# zumy_carrier_board.net
KiCad netlist of a schematic drawn in EAGLE
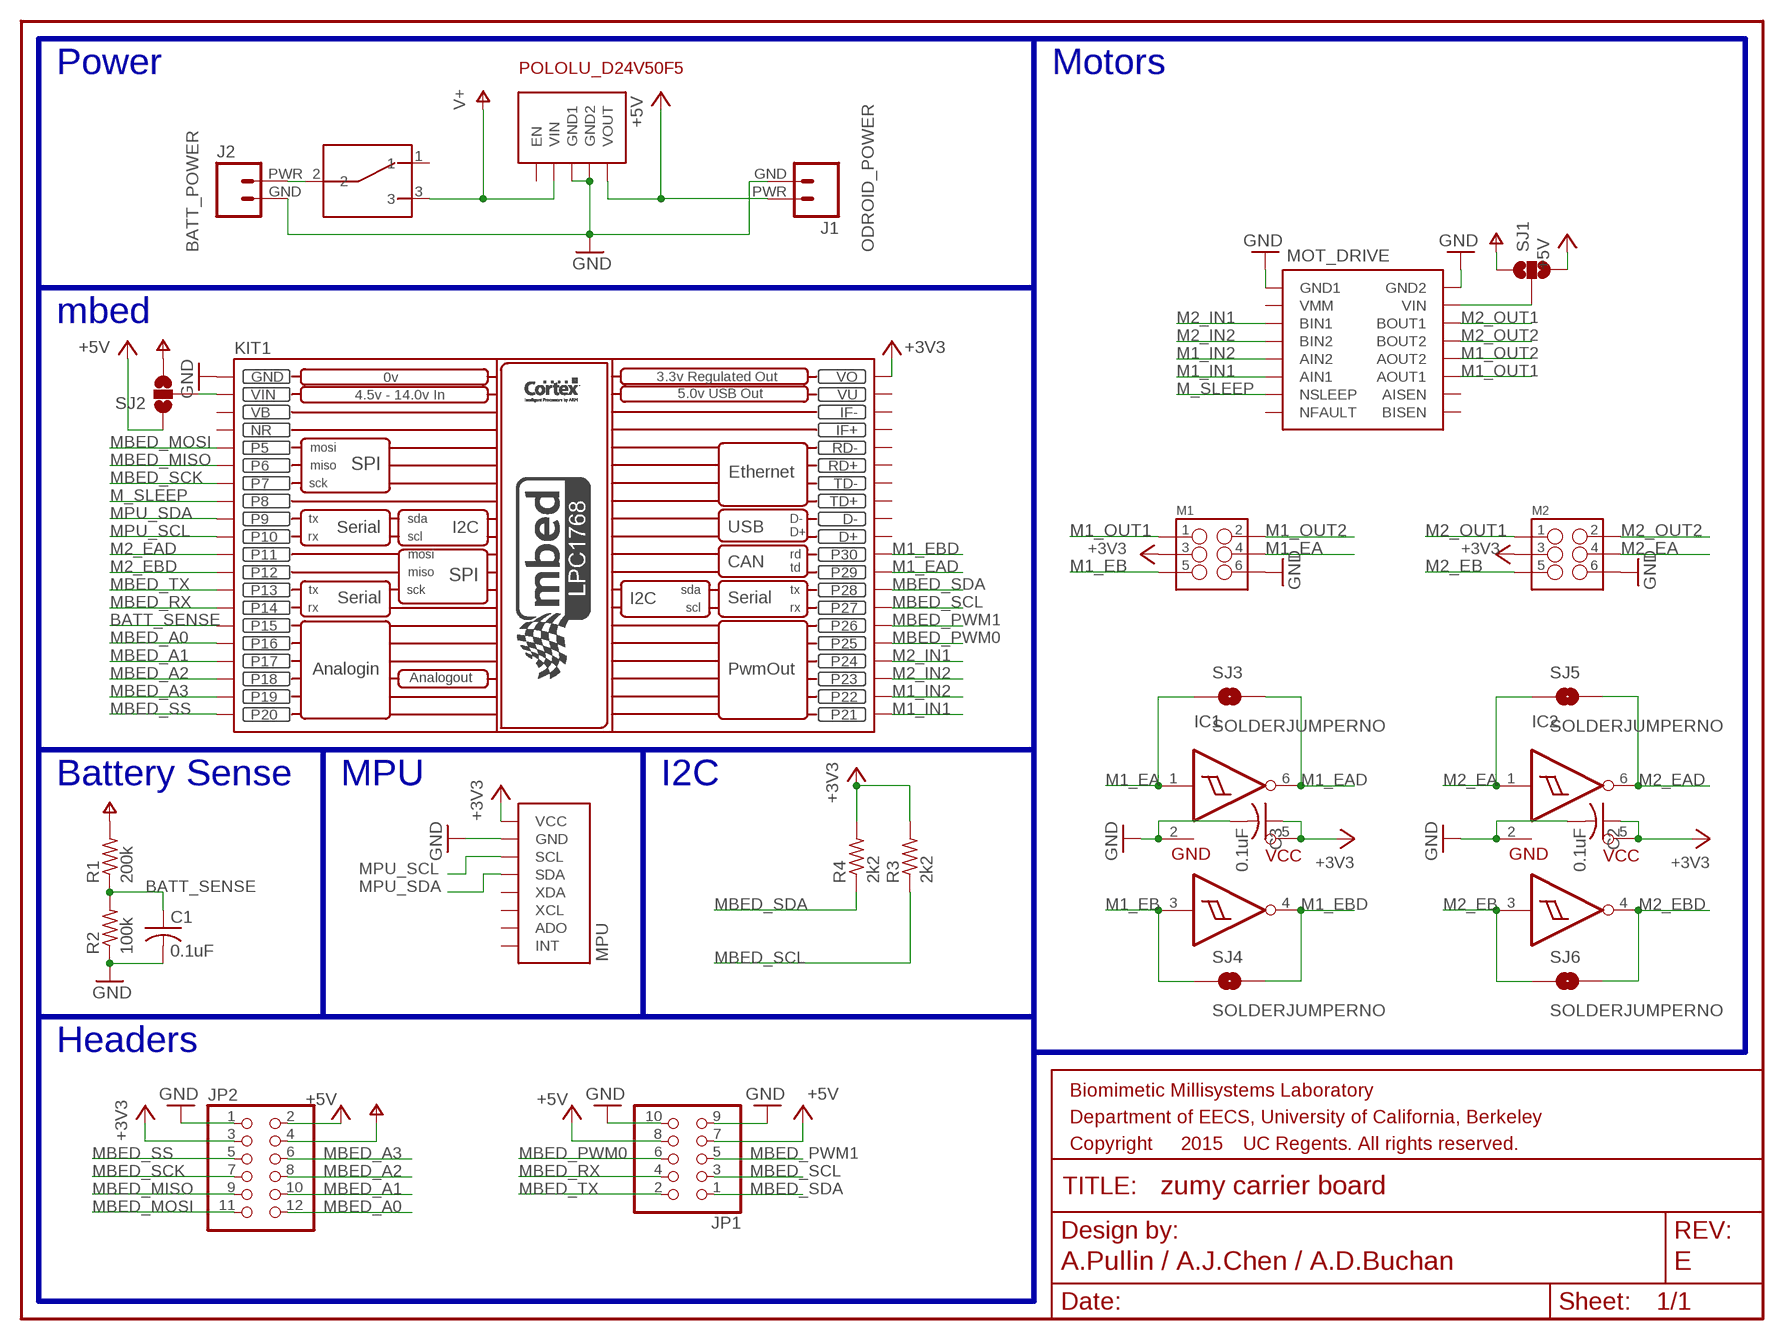
[diagram p0: schematic, sheet 1]

(export (version "E")
  (design (tool "Eeschema 10.0.6"))
  (components
    (comp (ref "C1")
      (value "0.1uF")
      (footprint "eagle-import:C1206")
      (libsource (lib "eagle-import") (part "C-USC1206"))
    )
    (comp (ref "C2")
      (value "0.1uF")
      (footprint "eagle-import:C1206")
      (libsource (lib "eagle-import") (part "C-USC1206"))
    )
    (comp (ref "C3")
      (value "0.1uF")
      (footprint "eagle-import:C1206")
      (libsource (lib "eagle-import") (part "C-USC1206"))
    )
    (comp (ref "IC1")
      (value "SN74AUP2G17")
      (footprint "eagle-import:SC-70-6")
      (libsource (lib "eagle-import") (part "SN74AUP2G17"))
    )
    (comp (ref "IC2")
      (value "SN74AUP2G17")
      (footprint "eagle-import:SC-70-6")
      (libsource (lib "eagle-import") (part "SN74AUP2G17"))
    )
    (comp (ref "J1")
      (value "ODROID_POWER")
      (footprint "eagle-import:ODOIRD_PWR")
      (libsource (lib "eagle-import") (part "ODROID_POWER"))
    )
    (comp (ref "J2")
      (value "BATT_POWER")
      (footprint "eagle-import:BATT_POWER")
      (libsource (lib "eagle-import") (part "BATT_POWER"))
    )
    (comp (ref "JP1")
      (value "PINHD-2X5")
      (footprint "eagle-import:2X05")
      (libsource (lib "eagle-import") (part "PINHD-2X5"))
    )
    (comp (ref "JP2")
      (value "PINHD-2X6")
      (footprint "eagle-import:2X06")
      (libsource (lib "eagle-import") (part "PINHD-2X6"))
    )
    (comp (ref "KIT1")
      (value "MBED_NXP_LPC1768")
      (footprint "eagle-import:MBED-KIT")
      (libsource (lib "eagle-import") (part "MBED_NXP_LPC1768"))
    )
    (comp (ref "M1")
      (value "M03X2SHROUD")
      (footprint "eagle-import:2X3-SHROUDED")
      (libsource (lib "eagle-import") (part "M03X2SHROUD"))
    )
    (comp (ref "M2")
      (value "M03X2SHROUD")
      (footprint "eagle-import:2X3-SHROUDED")
      (libsource (lib "eagle-import") (part "M03X2SHROUD"))
    )
    (comp (ref "MOT_DRIVE")
      (value "POLOLU_DRV8833_MODULE")
      (footprint "eagle-import:POLOLU_DRV8833_MODULE")
      (libsource (lib "eagle-import") (part "POLOLU_DRV8833_MODULE"))
    )
    (comp (ref "MPU")
      (value "ITG/MPU_MODULE")
      (footprint "eagle-import:ITG_MPU_MODULE")
      (libsource (lib "eagle-import") (part "ITG/MPU_MODULE"))
    )
    (comp (ref "R1")
      (value "200k")
      (footprint "eagle-import:R1206")
      (libsource (lib "eagle-import") (part "R-US_R1206"))
    )
    (comp (ref "R2")
      (value "100k")
      (footprint "eagle-import:R1206")
      (libsource (lib "eagle-import") (part "R-US_R1206"))
    )
    (comp (ref "R3")
      (value "2k2")
      (footprint "eagle-import:R1206")
      (libsource (lib "eagle-import") (part "R-US_R1206"))
    )
    (comp (ref "R4")
      (value "2k2")
      (footprint "eagle-import:R1206")
      (libsource (lib "eagle-import") (part "R-US_R1206"))
    )
    (comp (ref "SJ1")
      (value "SOLDERJUMPER_2WAYT")
      (footprint "eagle-import:SJ_2")
      (libsource (lib "eagle-import") (part "SOLDERJUMPER_2WAYT"))
    )
    (comp (ref "SJ2")
      (value "SOLDERJUMPER_2WAYT")
      (footprint "eagle-import:SJ_2")
      (libsource (lib "eagle-import") (part "SOLDERJUMPER_2WAYT"))
    )
    (comp (ref "SJ3")
      (value "SOLDERJUMPERNO")
      (footprint "eagle-import:SJ_2S-NO")
      (libsource (lib "eagle-import") (part "SOLDERJUMPERNO"))
    )
    (comp (ref "SJ4")
      (value "SOLDERJUMPERNO")
      (footprint "eagle-import:SJ_2S-NO")
      (libsource (lib "eagle-import") (part "SOLDERJUMPERNO"))
    )
    (comp (ref "SJ5")
      (value "SOLDERJUMPERNO")
      (footprint "eagle-import:SJ_2S-NO")
      (libsource (lib "eagle-import") (part "SOLDERJUMPERNO"))
    )
    (comp (ref "SJ6")
      (value "SOLDERJUMPERNO")
      (footprint "eagle-import:SJ_2S-NO")
      (libsource (lib "eagle-import") (part "SOLDERJUMPERNO"))
    )
    (comp (ref "SW1")
      (value "500SSP1S1M6QEA")
      (footprint "eagle-import:500SSP1S1M6QEA_SWITCH")
      (libsource (lib "eagle-import") (part "500SSP1S1M6QEA"))
    )
    (comp (ref "U$5")
      (value "POLOLU_D24V50F5")
      (footprint "eagle-import:POLOLU_D24V50F5")
      (libsource (lib "eagle-import") (part "POLOLU_D24V50F5"))
    )
  )
  (nets
    (net (code "1") (name "+3V3") (class "Default")
      (node (ref "C2") (pin "1") (pinfunction "1_1") (pintype "passive"))
      (node (ref "C3") (pin "1") (pinfunction "1_1") (pintype "passive"))
      (node (ref "IC1") (pin "5") (pinfunction "VCC_5") (pintype "output"))
      (node (ref "IC2") (pin "5") (pinfunction "VCC_5") (pintype "output"))
      (node (ref "JP2") (pin "3") (pinfunction "3_3") (pintype "passive"))
      (node (ref "KIT1") (pin "VOUT") (pinfunction "VO_VOUT") (pintype "power_in"))
      (node (ref "M1") (pin "3") (pinfunction "3_3") (pintype "bidirectional"))
      (node (ref "M2") (pin "3") (pinfunction "3_3") (pintype "bidirectional"))
      (node (ref "MPU") (pin "VCC") (pinfunction "VCC_VCC") (pintype "bidirectional"))
      (node (ref "R3") (pin "2") (pinfunction "2_2") (pintype "passive"))
      (node (ref "R4") (pin "2") (pinfunction "2_2") (pintype "passive"))
    )
    (net (code "2") (name "+5V") (class "Default")
      (node (ref "J1") (pin "PWR") (pinfunction "PWR_PWR") (pintype "passive"))
      (node (ref "JP1") (pin "7") (pinfunction "7_7") (pintype "passive"))
      (node (ref "JP1") (pin "8") (pinfunction "8_8") (pintype "passive"))
      (node (ref "JP2") (pin "2") (pinfunction "2_2") (pintype "passive"))
      (node (ref "SJ1") (pin "3") (pinfunction "3_3") (pintype "passive"))
      (node (ref "SJ2") (pin "1") (pinfunction "1_1") (pintype "passive"))
      (node (ref "U$5") (pin "VOUT") (pinfunction "VOUT_VOUT") (pintype "bidirectional"))
    )
    (net (code "3") (name "/BATT_SENSE") (class "Default")
      (node (ref "C1") (pin "1") (pinfunction "1_1") (pintype "passive"))
      (node (ref "KIT1") (pin "P$15") (pinfunction "P15_P$15") (pintype "bidirectional"))
      (node (ref "R1") (pin "1") (pinfunction "1_1") (pintype "passive"))
      (node (ref "R2") (pin "2") (pinfunction "2_2") (pintype "passive"))
    )
    (net (code "4") (name "/M1_EA") (class "Default")
      (node (ref "IC1") (pin "1") (pinfunction "1A_1") (pintype "input"))
      (node (ref "M1") (pin "4") (pinfunction "4_4") (pintype "bidirectional"))
      (node (ref "SJ3") (pin "1") (pinfunction "1_1") (pintype "passive"))
    )
    (net (code "5") (name "/M1_EAD") (class "Default")
      (node (ref "IC1") (pin "6") (pinfunction "1Y_6") (pintype "output"))
      (node (ref "KIT1") (pin "P$29") (pinfunction "P29_P$29") (pintype "bidirectional"))
      (node (ref "SJ3") (pin "2") (pinfunction "2_2") (pintype "passive"))
    )
    (net (code "6") (name "/M1_EB") (class "Default")
      (node (ref "IC1") (pin "3") (pinfunction "2A_3") (pintype "input"))
      (node (ref "M1") (pin "5") (pinfunction "5_5") (pintype "bidirectional"))
      (node (ref "SJ4") (pin "1") (pinfunction "1_1") (pintype "passive"))
    )
    (net (code "7") (name "/M1_EBD") (class "Default")
      (node (ref "IC1") (pin "4") (pinfunction "2Y_4") (pintype "output"))
      (node (ref "KIT1") (pin "P$30") (pinfunction "P30_P$30") (pintype "bidirectional"))
      (node (ref "SJ4") (pin "2") (pinfunction "2_2") (pintype "passive"))
    )
    (net (code "8") (name "/M1_IN1") (class "Default")
      (node (ref "KIT1") (pin "P$21") (pinfunction "P21_P$21") (pintype "bidirectional"))
      (node (ref "MOT_DRIVE") (pin "AIN1") (pinfunction "AIN1_AIN1") (pintype "bidirectional"))
    )
    (net (code "9") (name "/M1_IN2") (class "Default")
      (node (ref "KIT1") (pin "P$22") (pinfunction "P22_P$22") (pintype "bidirectional"))
      (node (ref "MOT_DRIVE") (pin "AIN2") (pinfunction "AIN2_AIN2") (pintype "bidirectional"))
    )
    (net (code "10") (name "/M1_OUT1") (class "Default")
      (node (ref "M1") (pin "1") (pinfunction "1_1") (pintype "bidirectional"))
      (node (ref "MOT_DRIVE") (pin "AOUT1") (pinfunction "AOUT1_AOUT1") (pintype "bidirectional"))
    )
    (net (code "11") (name "/M1_OUT2") (class "Default")
      (node (ref "M1") (pin "2") (pinfunction "2_2") (pintype "bidirectional"))
      (node (ref "MOT_DRIVE") (pin "AOUT2") (pinfunction "AOUT2_AOUT2") (pintype "bidirectional"))
    )
    (net (code "12") (name "/M2_EA") (class "Default")
      (node (ref "IC2") (pin "1") (pinfunction "1A_1") (pintype "input"))
      (node (ref "M2") (pin "4") (pinfunction "4_4") (pintype "bidirectional"))
      (node (ref "SJ5") (pin "1") (pinfunction "1_1") (pintype "passive"))
    )
    (net (code "13") (name "/M2_EAD") (class "Default")
      (node (ref "IC2") (pin "6") (pinfunction "1Y_6") (pintype "output"))
      (node (ref "KIT1") (pin "P$11") (pinfunction "P11_P$11") (pintype "bidirectional"))
      (node (ref "SJ5") (pin "2") (pinfunction "2_2") (pintype "passive"))
    )
    (net (code "14") (name "/M2_EB") (class "Default")
      (node (ref "IC2") (pin "3") (pinfunction "2A_3") (pintype "input"))
      (node (ref "M2") (pin "5") (pinfunction "5_5") (pintype "bidirectional"))
      (node (ref "SJ6") (pin "1") (pinfunction "1_1") (pintype "passive"))
    )
    (net (code "15") (name "/M2_EBD") (class "Default")
      (node (ref "IC2") (pin "4") (pinfunction "2Y_4") (pintype "output"))
      (node (ref "KIT1") (pin "P$12") (pinfunction "P12_P$12") (pintype "bidirectional"))
      (node (ref "SJ6") (pin "2") (pinfunction "2_2") (pintype "passive"))
    )
    (net (code "16") (name "/M2_IN1") (class "Default")
      (node (ref "KIT1") (pin "P$24") (pinfunction "P24_P$24") (pintype "bidirectional"))
      (node (ref "MOT_DRIVE") (pin "BIN1") (pinfunction "BIN1_BIN1") (pintype "bidirectional"))
    )
    (net (code "17") (name "/M2_IN2") (class "Default")
      (node (ref "KIT1") (pin "P$23") (pinfunction "P23_P$23") (pintype "bidirectional"))
      (node (ref "MOT_DRIVE") (pin "BIN2") (pinfunction "BIN2_BIN2") (pintype "bidirectional"))
    )
    (net (code "18") (name "/M2_OUT1") (class "Default")
      (node (ref "M2") (pin "1") (pinfunction "1_1") (pintype "bidirectional"))
      (node (ref "MOT_DRIVE") (pin "BOUT1") (pinfunction "BOUT1_BOUT1") (pintype "bidirectional"))
    )
    (net (code "19") (name "/M2_OUT2") (class "Default")
      (node (ref "M2") (pin "2") (pinfunction "2_2") (pintype "bidirectional"))
      (node (ref "MOT_DRIVE") (pin "BOUT2") (pinfunction "BOUT2_BOUT2") (pintype "bidirectional"))
    )
    (net (code "20") (name "/MBED_A0") (class "Default")
      (node (ref "JP2") (pin "12") (pinfunction "12_12") (pintype "passive"))
      (node (ref "KIT1") (pin "P$16") (pinfunction "P16_P$16") (pintype "bidirectional"))
    )
    (net (code "21") (name "/MBED_A1") (class "Default")
      (node (ref "JP2") (pin "10") (pinfunction "10_10") (pintype "passive"))
      (node (ref "KIT1") (pin "P$17") (pinfunction "P17_P$17") (pintype "bidirectional"))
    )
    (net (code "22") (name "/MBED_A2") (class "Default")
      (node (ref "JP2") (pin "8") (pinfunction "8_8") (pintype "passive"))
      (node (ref "KIT1") (pin "P$18") (pinfunction "P18_P$18") (pintype "bidirectional"))
    )
    (net (code "23") (name "/MBED_A3") (class "Default")
      (node (ref "JP2") (pin "6") (pinfunction "6_6") (pintype "passive"))
      (node (ref "KIT1") (pin "P$19") (pinfunction "P19_P$19") (pintype "bidirectional"))
    )
    (net (code "24") (name "/MBED_MISO") (class "Default")
      (node (ref "JP2") (pin "9") (pinfunction "9_9") (pintype "passive"))
      (node (ref "KIT1") (pin "P$6") (pinfunction "P6_P$6") (pintype "bidirectional"))
    )
    (net (code "25") (name "/MBED_MOSI") (class "Default")
      (node (ref "JP2") (pin "11") (pinfunction "11_11") (pintype "passive"))
      (node (ref "KIT1") (pin "P$5") (pinfunction "P5_P$5") (pintype "bidirectional"))
    )
    (net (code "26") (name "/MBED_PWM0") (class "Default")
      (node (ref "JP1") (pin "6") (pinfunction "6_6") (pintype "passive"))
      (node (ref "KIT1") (pin "P$25") (pinfunction "P25_P$25") (pintype "bidirectional"))
    )
    (net (code "27") (name "/MBED_PWM1") (class "Default")
      (node (ref "JP1") (pin "5") (pinfunction "5_5") (pintype "passive"))
      (node (ref "KIT1") (pin "P$26") (pinfunction "P26_P$26") (pintype "bidirectional"))
    )
    (net (code "28") (name "/MBED_RX") (class "Default")
      (node (ref "JP1") (pin "4") (pinfunction "4_4") (pintype "passive"))
      (node (ref "KIT1") (pin "P$14") (pinfunction "P14_P$14") (pintype "bidirectional"))
    )
    (net (code "29") (name "/MBED_SCK") (class "Default")
      (node (ref "JP2") (pin "7") (pinfunction "7_7") (pintype "passive"))
      (node (ref "KIT1") (pin "P$7") (pinfunction "P7_P$7") (pintype "bidirectional"))
    )
    (net (code "30") (name "/MBED_SCL") (class "Default")
      (node (ref "JP1") (pin "3") (pinfunction "3_3") (pintype "passive"))
      (node (ref "KIT1") (pin "P$27") (pinfunction "P27_P$27") (pintype "bidirectional"))
      (node (ref "R3") (pin "1") (pinfunction "1_1") (pintype "passive"))
    )
    (net (code "31") (name "/MBED_SDA") (class "Default")
      (node (ref "JP1") (pin "1") (pinfunction "1_1") (pintype "passive"))
      (node (ref "KIT1") (pin "P$28") (pinfunction "P28_P$28") (pintype "bidirectional"))
      (node (ref "R4") (pin "1") (pinfunction "1_1") (pintype "passive"))
    )
    (net (code "32") (name "/MBED_SS") (class "Default")
      (node (ref "JP2") (pin "5") (pinfunction "5_5") (pintype "passive"))
      (node (ref "KIT1") (pin "P$20") (pinfunction "P20_P$20") (pintype "bidirectional"))
    )
    (net (code "33") (name "/MBED_TX") (class "Default")
      (node (ref "JP1") (pin "2") (pinfunction "2_2") (pintype "passive"))
      (node (ref "KIT1") (pin "P$13") (pinfunction "P13_P$13") (pintype "bidirectional"))
    )
    (net (code "34") (name "/MPU_SCL") (class "Default")
      (node (ref "KIT1") (pin "P$10") (pinfunction "P10_P$10") (pintype "bidirectional"))
      (node (ref "MPU") (pin "SCL") (pinfunction "SCL_SCL") (pintype "bidirectional"))
    )
    (net (code "35") (name "/MPU_SDA") (class "Default")
      (node (ref "KIT1") (pin "P$9") (pinfunction "P9_P$9") (pintype "bidirectional"))
      (node (ref "MPU") (pin "SDA") (pinfunction "SDA_SDA") (pintype "bidirectional"))
    )
    (net (code "36") (name "/M_SLEEP") (class "Default")
      (node (ref "KIT1") (pin "P$8") (pinfunction "P8_P$8") (pintype "bidirectional"))
      (node (ref "MOT_DRIVE") (pin "NSLEEP") (pinfunction "NSLEEP_NSLEEP") (pintype "bidirectional"))
    )
    (net (code "37") (name "/NR") (class "Default")
      (node (ref "KIT1") (pin "NR") (pinfunction "NR_NR") (pintype "power_in"))
    )
    (net (code "38") (name "/VB") (class "Default")
      (node (ref "KIT1") (pin "VB") (pinfunction "VB_VB") (pintype "power_in"))
    )
    (net (code "39") (name "/VU") (class "Default")
      (node (ref "KIT1") (pin "VU") (pinfunction "VU_VU") (pintype "power_in"))
    )
    (net (code "40") (name "GND") (class "Default")
      (node (ref "C1") (pin "2") (pinfunction "2_2") (pintype "passive"))
      (node (ref "C2") (pin "2") (pinfunction "2_2") (pintype "passive"))
      (node (ref "C3") (pin "2") (pinfunction "2_2") (pintype "passive"))
      (node (ref "IC1") (pin "2") (pinfunction "GND_2") (pintype "input"))
      (node (ref "IC2") (pin "2") (pinfunction "GND_2") (pintype "input"))
      (node (ref "J1") (pin "GND") (pinfunction "GND_GND") (pintype "passive"))
      (node (ref "J2") (pin "GND") (pinfunction "GND_GND") (pintype "passive"))
      (node (ref "JP1") (pin "10") (pinfunction "10_10") (pintype "passive"))
      (node (ref "JP1") (pin "9") (pinfunction "9_9") (pintype "passive"))
      (node (ref "JP2") (pin "1") (pinfunction "1_1") (pintype "passive"))
      (node (ref "KIT1") (pin "GND") (pinfunction "GND_GND") (pintype "power_in"))
      (node (ref "M1") (pin "6") (pinfunction "6_6") (pintype "bidirectional"))
      (node (ref "M2") (pin "6") (pinfunction "6_6") (pintype "bidirectional"))
      (node (ref "MOT_DRIVE") (pin "GND1") (pinfunction "GND1_GND1") (pintype "bidirectional"))
      (node (ref "MOT_DRIVE") (pin "GND2") (pinfunction "GND2_GND2") (pintype "bidirectional"))
      (node (ref "MPU") (pin "GND") (pinfunction "GND_GND") (pintype "bidirectional"))
      (node (ref "R2") (pin "1") (pinfunction "1_1") (pintype "passive"))
      (node (ref "U$5") (pin "GND1") (pinfunction "GND1_GND1") (pintype "bidirectional"))
      (node (ref "U$5") (pin "GND2") (pinfunction "GND2_GND2") (pintype "bidirectional"))
    )
    (net (code "41") (name "Net-(J2-PadPWR)") (class "Default")
      (node (ref "J2") (pin "PWR") (pinfunction "PWR_PWR") (pintype "passive"))
      (node (ref "SW1") (pin "2") (pinfunction "2_2") (pintype "bidirectional"))
    )
    (net (code "42") (name "Net-(KIT1-PadVIN)") (class "Default")
      (node (ref "KIT1") (pin "VIN") (pinfunction "VIN_VIN") (pintype "power_in"))
      (node (ref "SJ2") (pin "2") (pinfunction "2_2") (pintype "passive"))
    )
    (net (code "43") (name "Net-(MOT_DRIVE-PadVIN)") (class "Default")
      (node (ref "MOT_DRIVE") (pin "VIN") (pinfunction "VIN_VIN") (pintype "bidirectional"))
      (node (ref "SJ1") (pin "2") (pinfunction "2_2") (pintype "passive"))
    )
    (net (code "44") (name "V+") (class "Default")
      (node (ref "JP2") (pin "4") (pinfunction "4_4") (pintype "passive"))
      (node (ref "R1") (pin "2") (pinfunction "2_2") (pintype "passive"))
      (node (ref "SJ1") (pin "1") (pinfunction "1_1") (pintype "passive"))
      (node (ref "SJ2") (pin "3") (pinfunction "3_3") (pintype "passive"))
      (node (ref "SW1") (pin "3") (pinfunction "3_3") (pintype "bidirectional"))
      (node (ref "U$5") (pin "VIN") (pinfunction "VIN_VIN") (pintype "bidirectional"))
    )
    (net (code "45") (name "unconnected-(KIT1-PadD+)") (class "Default")
      (node (ref "KIT1") (pin "D+") (pinfunction "D+_D+") (pintype "bidirectional"))
    )
    (net (code "46") (name "unconnected-(KIT1-PadD-)") (class "Default")
      (node (ref "KIT1") (pin "D-") (pinfunction "D-_D-") (pintype "bidirectional"))
    )
    (net (code "47") (name "unconnected-(KIT1-PadIF+)") (class "Default")
      (node (ref "KIT1") (pin "IF+") (pinfunction "IF+_IF+") (pintype "bidirectional"))
    )
    (net (code "48") (name "unconnected-(KIT1-PadIF-)") (class "Default")
      (node (ref "KIT1") (pin "IF-") (pinfunction "IF-_IF-") (pintype "bidirectional"))
    )
    (net (code "49") (name "unconnected-(KIT1-PadRD+)") (class "Default")
      (node (ref "KIT1") (pin "RD+") (pinfunction "RD+_RD+") (pintype "bidirectional"))
    )
    (net (code "50") (name "unconnected-(KIT1-PadRD-)") (class "Default")
      (node (ref "KIT1") (pin "RD-") (pinfunction "RD-_RD-") (pintype "bidirectional"))
    )
    (net (code "51") (name "unconnected-(KIT1-PadTD+)") (class "Default")
      (node (ref "KIT1") (pin "TD+") (pinfunction "TD+_TD+") (pintype "bidirectional"))
    )
    (net (code "52") (name "unconnected-(KIT1-PadTD-)") (class "Default")
      (node (ref "KIT1") (pin "TD-") (pinfunction "TD-_TD-") (pintype "bidirectional"))
    )
    (net (code "53") (name "unconnected-(MOT_DRIVE-PadAISEN)") (class "Default")
      (node (ref "MOT_DRIVE") (pin "AISEN") (pinfunction "AISEN_AISEN") (pintype "bidirectional"))
    )
    (net (code "54") (name "unconnected-(MOT_DRIVE-PadBISEN)") (class "Default")
      (node (ref "MOT_DRIVE") (pin "BISEN") (pinfunction "BISEN_BISEN") (pintype "bidirectional"))
    )
    (net (code "55") (name "unconnected-(MOT_DRIVE-PadNFAULT)") (class "Default")
      (node (ref "MOT_DRIVE") (pin "NFAULT") (pinfunction "NFAULT_NFAULT") (pintype "bidirectional"))
    )
    (net (code "56") (name "unconnected-(MOT_DRIVE-PadVMM)") (class "Default")
      (node (ref "MOT_DRIVE") (pin "VMM") (pinfunction "VMM_VMM") (pintype "bidirectional"))
    )
    (net (code "57") (name "unconnected-(MPU-PadADO)") (class "Default")
      (node (ref "MPU") (pin "ADO") (pinfunction "ADO_ADO") (pintype "bidirectional"))
    )
    (net (code "58") (name "unconnected-(MPU-PadINT)") (class "Default")
      (node (ref "MPU") (pin "INT") (pinfunction "INT_INT") (pintype "bidirectional"))
    )
    (net (code "59") (name "unconnected-(MPU-PadXCL)") (class "Default")
      (node (ref "MPU") (pin "XCL") (pinfunction "XCL_XCL") (pintype "bidirectional"))
    )
    (net (code "60") (name "unconnected-(MPU-PadXDA)") (class "Default")
      (node (ref "MPU") (pin "XDA") (pinfunction "XDA_XDA") (pintype "bidirectional"))
    )
    (net (code "61") (name "unconnected-(SW1-Pad1)") (class "Default")
      (node (ref "SW1") (pin "1") (pinfunction "1_1") (pintype "bidirectional"))
    )
    (net (code "62") (name "unconnected-(U$5-PadEN)") (class "Default")
      (node (ref "U$5") (pin "EN") (pinfunction "EN_EN") (pintype "bidirectional"))
    )
  )
)
